# 04_POWER.net
KiCad netlist of a schematic drawn in Altium Designer
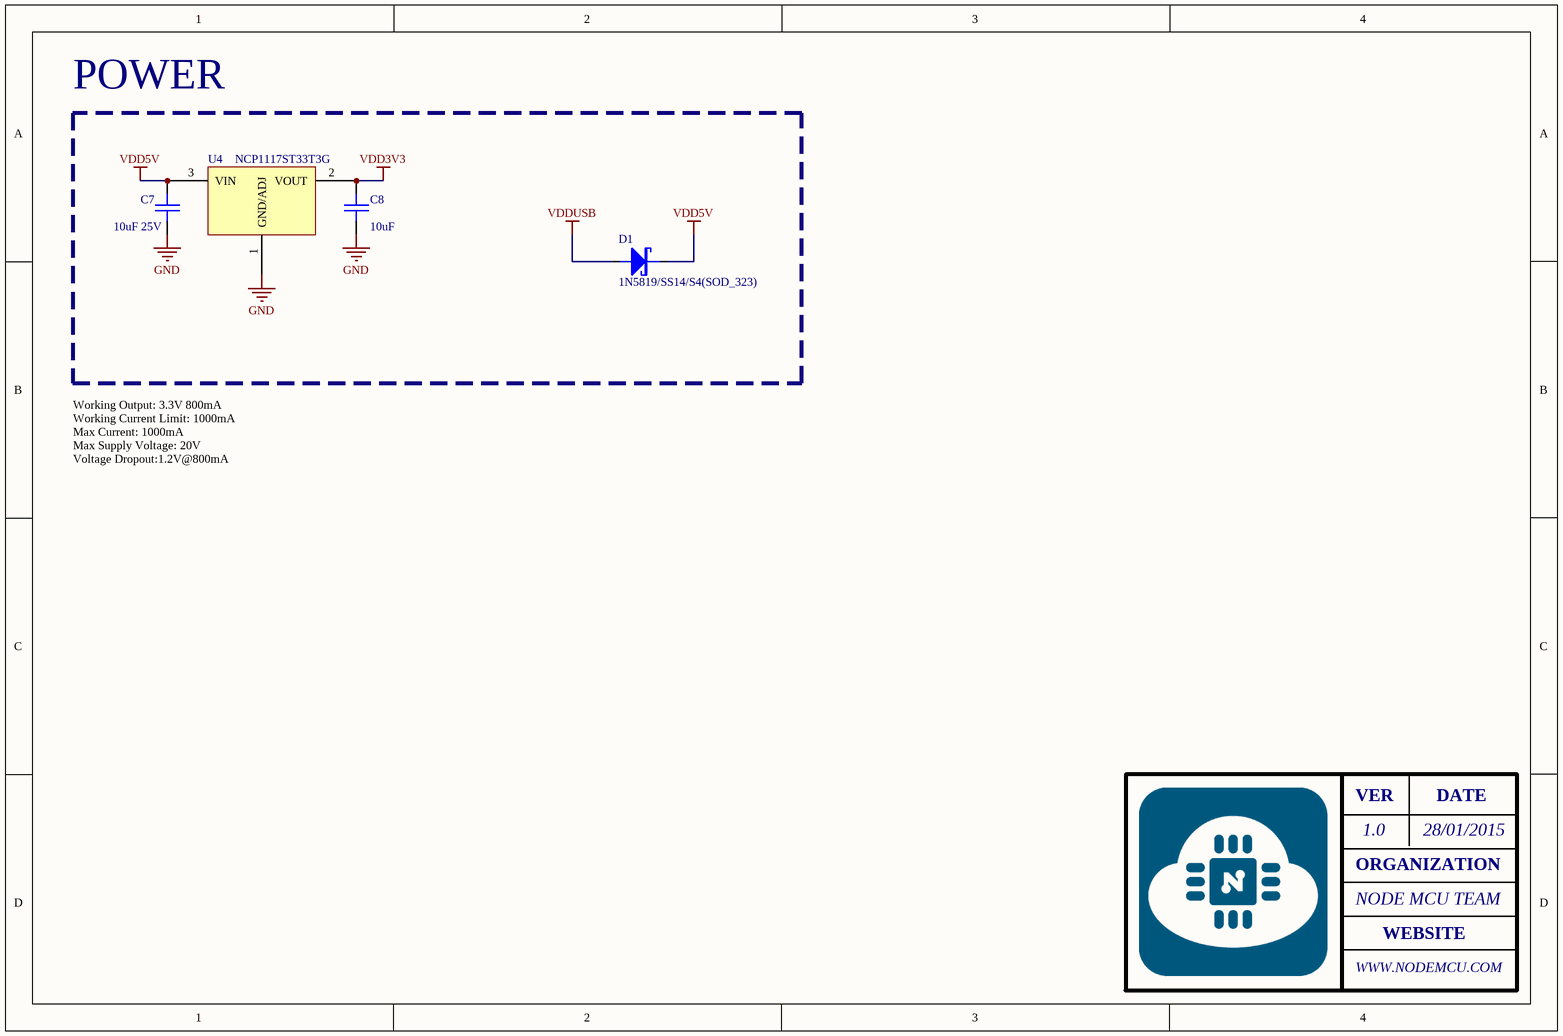
[diagram p0: 04_POWER.SchDoc]

(export (version "E")
  (design (tool "Eeschema 10.0.6"))
  (components
    (comp (ref "C7")
      (value "10uF 25V")
      (footprint "SMT_C_0805")
      (description "Surface mount capacitor 0805")
      (libsource (lib "Vowstar_Basic_Device") (part "SMT_C_0805"))
    )
    (comp (ref "C8")
      (value "10uF")
      (footprint "SMT_C_0603")
      (description "Surface mount capacitor 0402")
      (libsource (lib "Vowstar_Basic_Device") (part "SMT_C_0402"))
    )
    (comp (ref "D1")
      (value "1N5819/SS14/S4(SOD_323)")
      (footprint "SMT_DIODE_SOD_323")
      (description "Surface mount schottky diode SOD-323(0805) Package")
      (libsource (lib "Vowstar_Basic_Device") (part "SMT_DIODE_SCHOTTKY_SOD_323"))
    )
    (comp (ref "U4")
      (value "NCP1117ST33T3G")
      (footprint "SOT-223")
      (description "NCP1117, NCV1117. 1.0 A Low-Dropout Positive  Fixed and Adjustable  Voltage Regulators")
      (libsource (lib "Vowstar_IC_General") (part "NCP1117"))
    )
  )
  (nets
    (net (code "1") (name "GND") (class "Default")
      (node (ref "C7") (pin "2") (pinfunction "2_2") (pintype "passive"))
      (node (ref "C8") (pin "2") (pinfunction "2_2") (pintype "passive"))
      (node (ref "U4") (pin "1") (pinfunction "GND/ADJ_1") (pintype "passive"))
    )
    (net (code "2") (name "VDD3V3") (class "Default")
      (node (ref "C8") (pin "1") (pinfunction "1_1") (pintype "passive"))
      (node (ref "U4") (pin "2") (pinfunction "VOUT_2") (pintype "passive"))
    )
    (net (code "3") (name "VDD5V") (class "Default")
      (node (ref "C7") (pin "1") (pinfunction "1_1") (pintype "passive"))
      (node (ref "D1") (pin "2") (pinfunction "K_2") (pintype "passive"))
      (node (ref "U4") (pin "3") (pinfunction "VIN_3") (pintype "passive"))
    )
    (net (code "4") (name "VDDUSB") (class "Default")
      (node (ref "D1") (pin "1") (pinfunction "A_1") (pintype "passive"))
    )
  )
)
